# Schematic.net
KiCad netlist of a schematic drawn in EAGLE
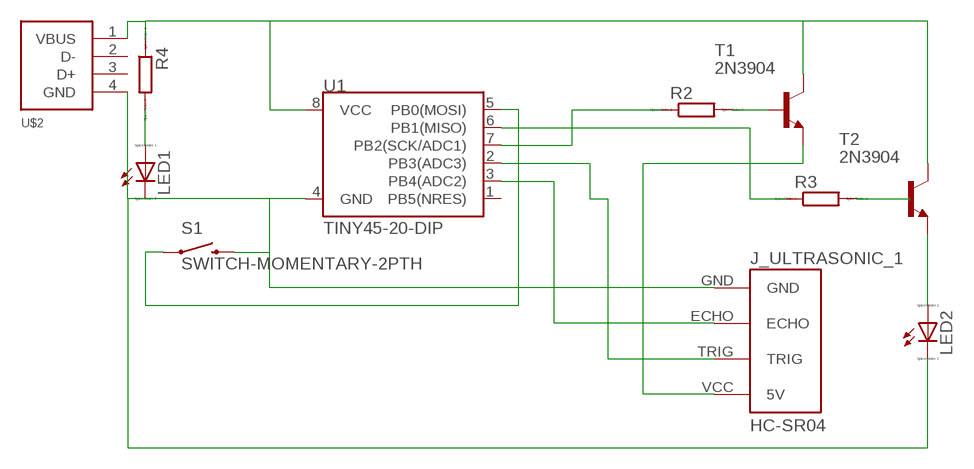
[diagram p0: schematic, sheet 1]

(export (version "E")
  (design (tool "Eeschema 10.0.6"))
  (components
    (comp (ref "J_ULTRASONIC_1")
      (value "HC-SR04")
      (footprint "eagle-import:HC-SR04_FOOTPRINT")
      (libsource (lib "eagle-import") (part "HC-SR04"))
    )
    (comp (ref "LED1")
      (value "LED_ELD260")
      (footprint "eagle-import:LED_LD260")
      (libsource (lib "eagle-import") (part "LED_ELD260"))
    )
    (comp (ref "LED2")
      (value "LED_ELD260")
      (footprint "eagle-import:LED_LD260")
      (libsource (lib "eagle-import") (part "LED_ELD260"))
    )
    (comp (ref "R2")
      (value "RR1206")
      (footprint "eagle-import:R1206")
      (libsource (lib "eagle-import") (part "RR1206"))
    )
    (comp (ref "R3")
      (value "RR1206")
      (footprint "eagle-import:R1206")
      (libsource (lib "eagle-import") (part "RR1206"))
    )
    (comp (ref "R4")
      (value "RR1206")
      (footprint "eagle-import:R1206")
      (libsource (lib "eagle-import") (part "RR1206"))
    )
    (comp (ref "S1")
      (value "SWITCH-MOMENTARY-2PTH")
      (footprint "eagle-import:TACTILE-PTH")
      (libsource (lib "eagle-import") (part "SWITCH-MOMENTARY-2PTH"))
    )
    (comp (ref "T1")
      (value "2N3904")
      (footprint "eagle-import:TO92")
      (libsource (lib "eagle-import") (part "2N3904"))
    )
    (comp (ref "T2")
      (value "2N3904")
      (footprint "eagle-import:TO92")
      (libsource (lib "eagle-import") (part "2N3904"))
    )
    (comp (ref "U$2")
      (value "USB-CON-4PIN")
      (footprint "eagle-import:USB-MALE-A-PCB")
      (libsource (lib "eagle-import") (part "USB-CON-4PIN"))
    )
    (comp (ref "U1")
      (value "TINY45-20-DIP")
      (footprint "eagle-import:DIP08")
      (libsource (lib "eagle-import") (part "ATTINY45TINY45-20-DIP"))
    )
  )
  (nets
    (net (code "1") (name "Net-(J_ULTRASONIC_1-5V)") (class "Default")
      (node (ref "J_ULTRASONIC_1") (pin "VCC") (pinfunction "5V_VCC") (pintype "bidirectional"))
      (node (ref "T1") (pin "3") (pinfunction "E_3") (pintype "passive"))
    )
    (net (code "2") (name "Net-(LED1-C)") (class "Default")
      (node (ref "J_ULTRASONIC_1") (pin "GND") (pinfunction "GND_GND") (pintype "bidirectional"))
      (node (ref "LED1") (pin "K") (pinfunction "C_K") (pintype "passive"))
      (node (ref "LED2") (pin "K") (pinfunction "C_K") (pintype "passive"))
      (node (ref "S1") (pin "3") (pinfunction "2_3") (pintype "passive"))
      (node (ref "U$2") (pin "4") (pinfunction "GND_4") (pintype "power_in"))
      (node (ref "U1") (pin "4") (pinfunction "GND_4") (pintype "bidirectional"))
    )
    (net (code "3") (name "Net-(LED1-PadA)") (class "Default")
      (node (ref "LED1") (pin "A") (pinfunction "A_A") (pintype "passive"))
      (node (ref "R4") (pin "2") (pinfunction "2_2") (pintype "passive"))
    )
    (net (code "4") (name "Net-(T1-B)") (class "Default")
      (node (ref "R2") (pin "2") (pinfunction "2_2") (pintype "passive"))
      (node (ref "T1") (pin "2") (pinfunction "B_2") (pintype "passive"))
    )
    (net (code "5") (name "Net-(T1-C)") (class "Default")
      (node (ref "R4") (pin "1") (pinfunction "1_1") (pintype "passive"))
      (node (ref "T1") (pin "1") (pinfunction "C_1") (pintype "passive"))
      (node (ref "T2") (pin "1") (pinfunction "C_1") (pintype "passive"))
      (node (ref "U$2") (pin "1") (pinfunction "VBUS_1") (pintype "power_in"))
      (node (ref "U1") (pin "8") (pinfunction "VCC_8") (pintype "bidirectional"))
    )
    (net (code "6") (name "Net-(T2-B)") (class "Default")
      (node (ref "R3") (pin "2") (pinfunction "2_2") (pintype "passive"))
      (node (ref "T2") (pin "2") (pinfunction "B_2") (pintype "passive"))
    )
    (net (code "7") (name "Net-(T2-E)") (class "Default")
      (node (ref "LED2") (pin "A") (pinfunction "A_A") (pintype "passive"))
      (node (ref "T2") (pin "3") (pinfunction "E_3") (pintype "passive"))
    )
    (net (code "8") (name "Net-(U1-PB0(MOSI))") (class "Default")
      (node (ref "S1") (pin "1") (pinfunction "1_1") (pintype "passive"))
      (node (ref "U1") (pin "5") (pinfunction "PB0(MOSI)_5") (pintype "bidirectional"))
    )
    (net (code "9") (name "Net-(U1-PB1(MISO))") (class "Default")
      (node (ref "R3") (pin "1") (pinfunction "1_1") (pintype "passive"))
      (node (ref "U1") (pin "6") (pinfunction "PB1(MISO)_6") (pintype "bidirectional"))
    )
    (net (code "10") (name "Net-(U1-PB2(SCK{slash}ADC1))") (class "Default")
      (node (ref "R2") (pin "1") (pinfunction "1_1") (pintype "passive"))
      (node (ref "U1") (pin "7") (pinfunction "PB2(SCK/ADC1)_7") (pintype "bidirectional"))
    )
    (net (code "11") (name "Net-(U1-PB3(ADC3))") (class "Default")
      (node (ref "J_ULTRASONIC_1") (pin "TRIG") (pinfunction "TRIG_TRIG") (pintype "bidirectional"))
      (node (ref "U1") (pin "2") (pinfunction "PB3(ADC3)_2") (pintype "bidirectional"))
    )
    (net (code "12") (name "Net-(U1-PB4(ADC2))") (class "Default")
      (node (ref "J_ULTRASONIC_1") (pin "ECHO") (pinfunction "ECHO_ECHO") (pintype "bidirectional"))
      (node (ref "U1") (pin "3") (pinfunction "PB4(ADC2)_3") (pintype "bidirectional"))
    )
    (net (code "13") (name "unconnected-(U$2-D+-Pad3)") (class "Default")
      (node (ref "U$2") (pin "3") (pinfunction "D+_3") (pintype "bidirectional"))
    )
    (net (code "14") (name "unconnected-(U$2-D--Pad2)") (class "Default")
      (node (ref "U$2") (pin "2") (pinfunction "D-_2") (pintype "bidirectional"))
    )
    (net (code "15") (name "unconnected-(U1-PB5(NRES)-Pad1)") (class "Default")
      (node (ref "U1") (pin "1") (pinfunction "PB5(NRES)_1") (pintype "bidirectional"))
    )
  )
)
